# IO_Driver.net
KiCad netlist of a schematic drawn in Altium Designer
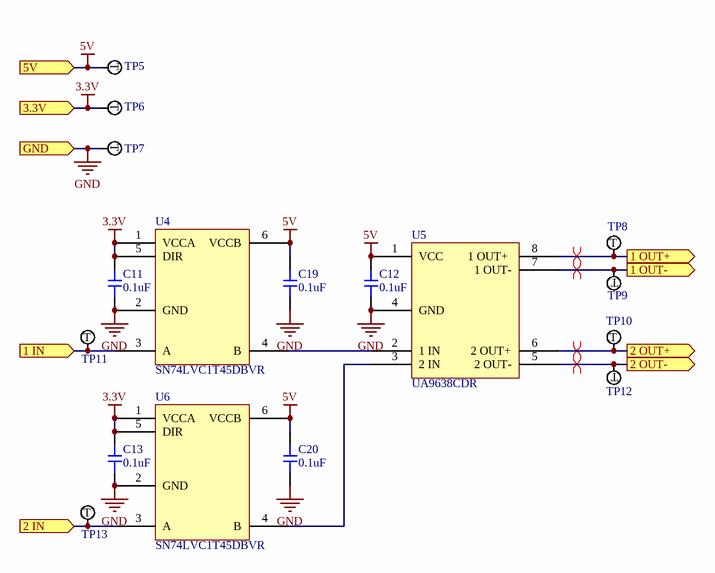
[diagram p0: IO_Driver.SchDoc]

(export (version "E")
  (design (tool "Eeschema 10.0.6"))
  (components
    (comp (ref "C11")
      (value "0.1uF")
      (footprint "0603-CAP")
      (description "0.1µF ±10% 25V Ceramic Capacitor X7R 0603 (1608 Metric)")
      (fields (field (name "Comment") "CC0603KRX7R8BB104"))
      (libsource (lib "IO_Converter") (part "Capacitor 0.1uF"))
    )
    (comp (ref "C12")
      (value "0.1uF")
      (footprint "0603-CAP")
      (description "0.1µF ±10% 25V Ceramic Capacitor X7R 0603 (1608 Metric)")
      (fields (field (name "Comment") "CC0603KRX7R8BB104"))
      (libsource (lib "IO_Converter") (part "Capacitor 0.1uF"))
    )
    (comp (ref "C13")
      (value "0.1uF")
      (footprint "0603-CAP")
      (description "0.1µF ±10% 25V Ceramic Capacitor X7R 0603 (1608 Metric)")
      (fields (field (name "Comment") "CC0603KRX7R8BB104"))
      (libsource (lib "IO_Converter") (part "Capacitor 0.1uF"))
    )
    (comp (ref "C19")
      (value "0.1uF")
      (footprint "0603-CAP")
      (description "0.1µF ±10% 25V Ceramic Capacitor X7R 0603 (1608 Metric)")
      (fields (field (name "Comment") "CC0603KRX7R8BB104"))
      (libsource (lib "IO_Converter") (part "Capacitor 0.1uF"))
    )
    (comp (ref "C20")
      (value "0.1uF")
      (footprint "0603-CAP")
      (description "0.1µF ±10% 25V Ceramic Capacitor X7R 0603 (1608 Metric)")
      (fields (field (name "Comment") "CC0603KRX7R8BB104"))
      (libsource (lib "IO_Converter") (part "Capacitor 0.1uF"))
    )
    (comp (ref "TP5")
      (value "RCU-0C")
      (footprint "RCU-0C")
      (description "PC TEST POINT NATURAL")
      (libsource (lib "IO_Converter") (part "Test Point"))
    )
    (comp (ref "TP6")
      (value "RCU-0C")
      (footprint "RCU-0C")
      (description "PC TEST POINT NATURAL")
      (libsource (lib "IO_Converter") (part "Test Point"))
    )
    (comp (ref "TP7")
      (value "RCU-0C")
      (footprint "RCU-0C")
      (description "PC TEST POINT NATURAL")
      (libsource (lib "IO_Converter") (part "Test Point"))
    )
    (comp (ref "TP8")
      (value "RCU-0C")
      (footprint "RCU-0C")
      (description "PC TEST POINT NATURAL")
      (libsource (lib "IO_Converter") (part "Test Point"))
    )
    (comp (ref "TP9")
      (value "RCU-0C")
      (footprint "RCU-0C")
      (description "PC TEST POINT NATURAL")
      (libsource (lib "IO_Converter") (part "Test Point"))
    )
    (comp (ref "TP10")
      (value "RCU-0C")
      (footprint "RCU-0C")
      (description "PC TEST POINT NATURAL")
      (libsource (lib "IO_Converter") (part "Test Point"))
    )
    (comp (ref "TP11")
      (value "RCU-0C")
      (footprint "RCU-0C")
      (description "PC TEST POINT NATURAL")
      (libsource (lib "IO_Converter") (part "Test Point"))
    )
    (comp (ref "TP12")
      (value "RCU-0C")
      (footprint "RCU-0C")
      (description "PC TEST POINT NATURAL")
      (libsource (lib "IO_Converter") (part "Test Point"))
    )
    (comp (ref "TP13")
      (value "RCU-0C")
      (footprint "RCU-0C")
      (description "PC TEST POINT NATURAL")
      (libsource (lib "IO_Converter") (part "Test Point"))
    )
    (comp (ref "U4")
      (value "SN74LVC1T45DBVR")
      (footprint "SOT95P280X145-6N")
      (description "IC TRNSLTR BIDIRECTIONAL SOT23-6")
      (libsource (lib "IO_Converter") (part "SN74LVC1T45DBVR"))
    )
    (comp (ref "U5")
      (value "UA9638CDR")
      (footprint "SOIC127P600X175-8N")
      (description "IC DRIVER 2/0 8SOIC")
      (libsource (lib "IO_Converter") (part "UA9638CDR"))
    )
    (comp (ref "U6")
      (value "SN74LVC1T45DBVR")
      (footprint "SOT95P280X145-6N")
      (description "IC TRNSLTR BIDIRECTIONAL SOT23-6")
      (libsource (lib "IO_Converter") (part "SN74LVC1T45DBVR"))
    )
  )
  (nets
    (net (code "1") (name "/1 IN") (class "Default")
      (node (ref "TP11") (pin "1") (pinfunction "1_1") (pintype "passive"))
      (node (ref "U4") (pin "3") (pinfunction "A_3") (pintype "passive"))
    )
    (net (code "2") (name "/1 OUT+") (class "Default")
      (node (ref "TP8") (pin "1") (pinfunction "1_1") (pintype "passive"))
      (node (ref "U5") (pin "8") (pinfunction "1_OUT+_8") (pintype "passive"))
    )
    (net (code "3") (name "/1 OUT-") (class "Default")
      (node (ref "TP9") (pin "1") (pinfunction "1_1") (pintype "passive"))
      (node (ref "U5") (pin "7") (pinfunction "1_OUT-_7") (pintype "passive"))
    )
    (net (code "4") (name "/2 IN") (class "Default")
      (node (ref "TP13") (pin "1") (pinfunction "1_1") (pintype "passive"))
      (node (ref "U6") (pin "3") (pinfunction "A_3") (pintype "passive"))
    )
    (net (code "5") (name "/2 OUT+") (class "Default")
      (node (ref "TP10") (pin "1") (pinfunction "1_1") (pintype "passive"))
      (node (ref "U5") (pin "6") (pinfunction "2_OUT+_6") (pintype "passive"))
    )
    (net (code "6") (name "/2 OUT-") (class "Default")
      (node (ref "TP12") (pin "1") (pinfunction "1_1") (pintype "passive"))
      (node (ref "U5") (pin "5") (pinfunction "2_OUT-_5") (pintype "passive"))
    )
    (net (code "7") (name "3.3V") (class "Default")
      (node (ref "C11") (pin "2") (pinfunction "2_2") (pintype "passive"))
      (node (ref "C13") (pin "2") (pinfunction "2_2") (pintype "passive"))
      (node (ref "TP6") (pin "1") (pinfunction "1_1") (pintype "passive"))
      (node (ref "U4") (pin "1") (pinfunction "VCCA_1") (pintype "passive"))
      (node (ref "U4") (pin "5") (pinfunction "DIR_5") (pintype "passive"))
      (node (ref "U6") (pin "1") (pinfunction "VCCA_1") (pintype "passive"))
      (node (ref "U6") (pin "5") (pinfunction "DIR_5") (pintype "passive"))
    )
    (net (code "8") (name "5V") (class "Default")
      (node (ref "C12") (pin "2") (pinfunction "2_2") (pintype "passive"))
      (node (ref "C19") (pin "2") (pinfunction "2_2") (pintype "passive"))
      (node (ref "C20") (pin "2") (pinfunction "2_2") (pintype "passive"))
      (node (ref "TP5") (pin "1") (pinfunction "1_1") (pintype "passive"))
      (node (ref "U4") (pin "6") (pinfunction "VCCB_6") (pintype "passive"))
      (node (ref "U5") (pin "1") (pinfunction "VCC_1") (pintype "passive"))
      (node (ref "U6") (pin "6") (pinfunction "VCCB_6") (pintype "passive"))
    )
    (net (code "9") (name "GND") (class "Default")
      (node (ref "C11") (pin "1") (pinfunction "1_1") (pintype "passive"))
      (node (ref "C12") (pin "1") (pinfunction "1_1") (pintype "passive"))
      (node (ref "C13") (pin "1") (pinfunction "1_1") (pintype "passive"))
      (node (ref "C19") (pin "1") (pinfunction "1_1") (pintype "passive"))
      (node (ref "C20") (pin "1") (pinfunction "1_1") (pintype "passive"))
      (node (ref "TP7") (pin "1") (pinfunction "1_1") (pintype "passive"))
      (node (ref "U4") (pin "2") (pinfunction "GND_2") (pintype "passive"))
      (node (ref "U5") (pin "4") (pinfunction "GND_4") (pintype "passive"))
      (node (ref "U6") (pin "2") (pinfunction "GND_2") (pintype "passive"))
    )
    (net (code "10") (name "Net-(U4-B)") (class "Default")
      (node (ref "U4") (pin "4") (pinfunction "B_4") (pintype "passive"))
      (node (ref "U5") (pin "2") (pinfunction "1_IN_2") (pintype "passive"))
    )
    (net (code "11") (name "Net-(U5-2_IN)") (class "Default")
      (node (ref "U5") (pin "3") (pinfunction "2_IN_3") (pintype "passive"))
      (node (ref "U6") (pin "4") (pinfunction "B_4") (pintype "passive"))
    )
  )
)
